# ads8330.net
KiCad netlist of a schematic drawn in EAGLE
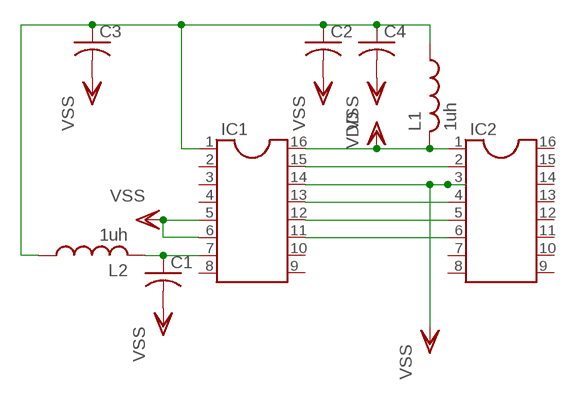
[diagram p0: schematic, sheet 1]

(export (version "E")
  (design (tool "Eeschema 10.0.6"))
  (components
    (comp (ref "C1")
      (value "C-US025-025X050")
      (footprint "eagle-import:C025-025X050")
      (libsource (lib "eagle-import") (part "C-US025-025X050"))
    )
    (comp (ref "C2")
      (value "C-US025-025X050")
      (footprint "eagle-import:C025-025X050")
      (libsource (lib "eagle-import") (part "C-US025-025X050"))
    )
    (comp (ref "C3")
      (value "C-US025-025X050")
      (footprint "eagle-import:C025-025X050")
      (libsource (lib "eagle-import") (part "C-US025-025X050"))
    )
    (comp (ref "C4")
      (value "C-US025-025X050")
      (footprint "eagle-import:C025-025X050")
      (libsource (lib "eagle-import") (part "C-US025-025X050"))
    )
    (comp (ref "IC1")
      (value "DIL16S")
      (footprint "eagle-import:SOCKET-16")
      (libsource (lib "eagle-import") (part "DIL16S"))
    )
    (comp (ref "IC2")
      (value "DIL16S")
      (footprint "eagle-import:SOCKET-16")
      (libsource (lib "eagle-import") (part "DIL16S"))
    )
    (comp (ref "L1")
      (value "1uh")
      (footprint "eagle-import:0204_7")
      (libsource (lib "eagle-import") (part "L-US0204/7"))
    )
    (comp (ref "L2")
      (value "1uh")
      (footprint "eagle-import:0204_7")
      (libsource (lib "eagle-import") (part "L-US0204/7"))
    )
  )
  (nets
    (net (code "1") (name "Net-(C1-Pad1)") (class "Default")
      (node (ref "C1") (pin "1") (pinfunction "1_1") (pintype "passive"))
      (node (ref "IC1") (pin "7") (pinfunction "7_7") (pintype "passive"))
      (node (ref "L2") (pin "2") (pinfunction "2_2") (pintype "passive"))
    )
    (net (code "2") (name "Net-(C2-Pad1)") (class "Default")
      (node (ref "C2") (pin "1") (pinfunction "1_1") (pintype "passive"))
      (node (ref "C3") (pin "1") (pinfunction "1_1") (pintype "passive"))
      (node (ref "C4") (pin "1") (pinfunction "1_1") (pintype "passive"))
      (node (ref "IC1") (pin "1") (pinfunction "1_1") (pintype "passive"))
      (node (ref "L1") (pin "1") (pinfunction "1_1") (pintype "passive"))
      (node (ref "L2") (pin "1") (pinfunction "1_1") (pintype "passive"))
    )
    (net (code "3") (name "Net-(IC1-Pad11)") (class "Default")
      (node (ref "IC1") (pin "11") (pinfunction "11_11") (pintype "passive"))
      (node (ref "IC2") (pin "6") (pinfunction "6_6") (pintype "passive"))
    )
    (net (code "4") (name "Net-(IC1-Pad12)") (class "Default")
      (node (ref "IC1") (pin "12") (pinfunction "12_12") (pintype "passive"))
      (node (ref "IC2") (pin "5") (pinfunction "5_5") (pintype "passive"))
    )
    (net (code "5") (name "Net-(IC1-Pad13)") (class "Default")
      (node (ref "IC1") (pin "13") (pinfunction "13_13") (pintype "passive"))
      (node (ref "IC2") (pin "4") (pinfunction "4_4") (pintype "passive"))
    )
    (net (code "6") (name "Net-(IC1-Pad15)") (class "Default")
      (node (ref "IC1") (pin "15") (pinfunction "15_15") (pintype "passive"))
      (node (ref "IC2") (pin "2") (pinfunction "2_2") (pintype "passive"))
    )
    (net (code "7") (name "VDD") (class "Default")
      (node (ref "IC1") (pin "16") (pinfunction "16_16") (pintype "passive"))
      (node (ref "IC2") (pin "1") (pinfunction "1_1") (pintype "passive"))
      (node (ref "L1") (pin "2") (pinfunction "2_2") (pintype "passive"))
    )
    (net (code "8") (name "VSS") (class "Default")
      (node (ref "C1") (pin "2") (pinfunction "2_2") (pintype "passive"))
      (node (ref "C2") (pin "2") (pinfunction "2_2") (pintype "passive"))
      (node (ref "C3") (pin "2") (pinfunction "2_2") (pintype "passive"))
      (node (ref "C4") (pin "2") (pinfunction "2_2") (pintype "passive"))
      (node (ref "IC1") (pin "14") (pinfunction "14_14") (pintype "passive"))
      (node (ref "IC1") (pin "5") (pinfunction "5_5") (pintype "passive"))
      (node (ref "IC1") (pin "6") (pinfunction "6_6") (pintype "passive"))
      (node (ref "IC2") (pin "3") (pinfunction "3_3") (pintype "passive"))
    )
    (net (code "9") (name "unconnected-(IC1-Pad2)") (class "Default")
      (node (ref "IC1") (pin "2") (pinfunction "2_2") (pintype "passive"))
    )
    (net (code "10") (name "unconnected-(IC1-Pad3)") (class "Default")
      (node (ref "IC1") (pin "3") (pinfunction "3_3") (pintype "passive"))
    )
    (net (code "11") (name "unconnected-(IC1-Pad4)") (class "Default")
      (node (ref "IC1") (pin "4") (pinfunction "4_4") (pintype "passive"))
    )
    (net (code "12") (name "unconnected-(IC1-Pad8)") (class "Default")
      (node (ref "IC1") (pin "8") (pinfunction "8_8") (pintype "passive"))
    )
    (net (code "13") (name "unconnected-(IC1-Pad9)") (class "Default")
      (node (ref "IC1") (pin "9") (pinfunction "9_9") (pintype "passive"))
    )
    (net (code "14") (name "unconnected-(IC1-Pad10)") (class "Default")
      (node (ref "IC1") (pin "10") (pinfunction "10_10") (pintype "passive"))
    )
    (net (code "15") (name "unconnected-(IC2-Pad7)") (class "Default")
      (node (ref "IC2") (pin "7") (pinfunction "7_7") (pintype "passive"))
    )
    (net (code "16") (name "unconnected-(IC2-Pad8)") (class "Default")
      (node (ref "IC2") (pin "8") (pinfunction "8_8") (pintype "passive"))
    )
    (net (code "17") (name "unconnected-(IC2-Pad9)") (class "Default")
      (node (ref "IC2") (pin "9") (pinfunction "9_9") (pintype "passive"))
    )
    (net (code "18") (name "unconnected-(IC2-Pad10)") (class "Default")
      (node (ref "IC2") (pin "10") (pinfunction "10_10") (pintype "passive"))
    )
    (net (code "19") (name "unconnected-(IC2-Pad11)") (class "Default")
      (node (ref "IC2") (pin "11") (pinfunction "11_11") (pintype "passive"))
    )
    (net (code "20") (name "unconnected-(IC2-Pad12)") (class "Default")
      (node (ref "IC2") (pin "12") (pinfunction "12_12") (pintype "passive"))
    )
    (net (code "21") (name "unconnected-(IC2-Pad13)") (class "Default")
      (node (ref "IC2") (pin "13") (pinfunction "13_13") (pintype "passive"))
    )
    (net (code "22") (name "unconnected-(IC2-Pad14)") (class "Default")
      (node (ref "IC2") (pin "14") (pinfunction "14_14") (pintype "passive"))
    )
    (net (code "23") (name "unconnected-(IC2-Pad15)") (class "Default")
      (node (ref "IC2") (pin "15") (pinfunction "15_15") (pintype "passive"))
    )
    (net (code "24") (name "unconnected-(IC2-Pad16)") (class "Default")
      (node (ref "IC2") (pin "16") (pinfunction "16_16") (pintype "passive"))
    )
  )
)
